# i2c_erm1602_encoder.net
KiCad netlist of a schematic drawn in EAGLE
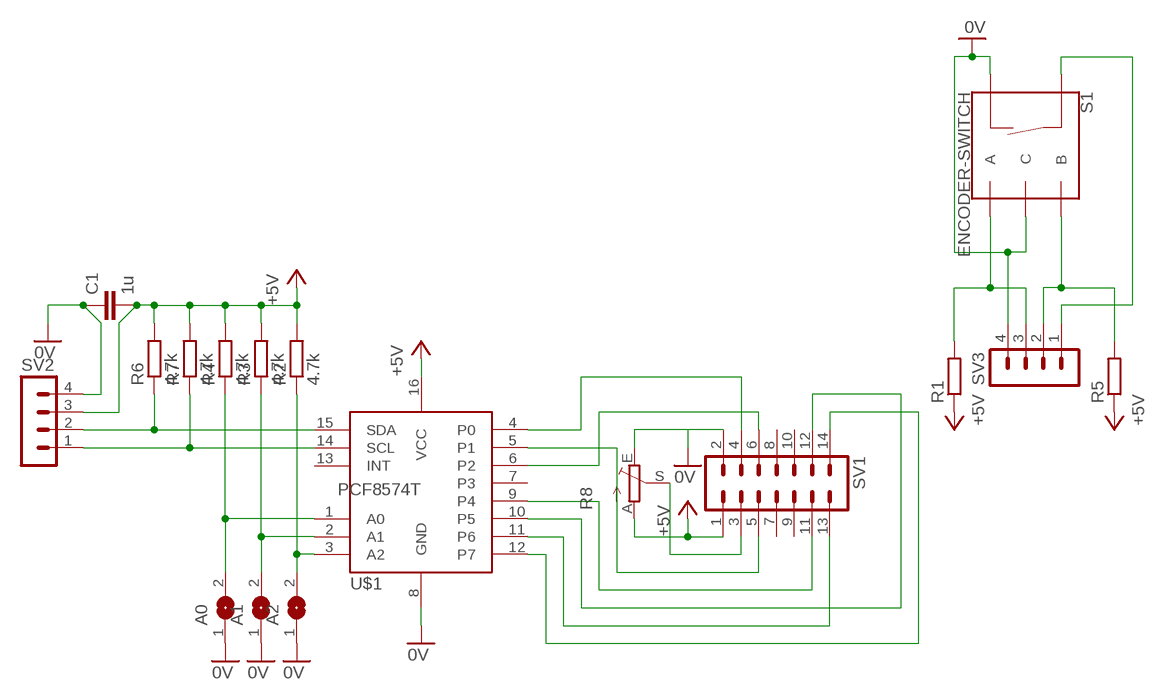
[diagram p0: schematic, sheet 1]

(export (version "E")
  (design (tool "Eeschema 10.0.6"))
  (components
    (comp (ref "A0") (value "SJ") (footprint "eagle-import:SJ") (libsource (lib "eagle-import") (part "SJ")))
    (comp (ref "A1") (value "SJ") (footprint "eagle-import:SJ") (libsource (lib "eagle-import") (part "SJ")))
    (comp (ref "A2") (value "SJ") (footprint "eagle-import:SJ") (libsource (lib "eagle-import") (part "SJ")))
    (comp (ref "C1")
      (value "1u")
      (footprint "eagle-import:C1206K")
      (libsource (lib "eagle-import") (part "C-EUC1206K"))
    )
    (comp (ref "R1")
      (value "R-EU_0204/5")
      (footprint "eagle-import:0204_5")
      (libsource (lib "eagle-import") (part "R-EU_0204/5"))
    )
    (comp (ref "R2")
      (value "4.7k")
      (footprint "eagle-import:0204_5")
      (libsource (lib "eagle-import") (part "R-EU_0204/5"))
    )
    (comp (ref "R3")
      (value "4.7k")
      (footprint "eagle-import:0204_5")
      (libsource (lib "eagle-import") (part "R-EU_0204/5"))
    )
    (comp (ref "R4")
      (value "4.7k")
      (footprint "eagle-import:0204_5")
      (libsource (lib "eagle-import") (part "R-EU_0204/5"))
    )
    (comp (ref "R5")
      (value "R-EU_0204/5")
      (footprint "eagle-import:0204_5")
      (libsource (lib "eagle-import") (part "R-EU_0204/5"))
    )
    (comp (ref "R6")
      (value "4.7k")
      (footprint "eagle-import:0204_5")
      (libsource (lib "eagle-import") (part "R-EU_0204/5"))
    )
    (comp (ref "R7")
      (value "4.7k")
      (footprint "eagle-import:0204_5")
      (libsource (lib "eagle-import") (part "R-EU_0204/5"))
    )
    (comp (ref "R8")
      (value "TRIM_EU-B25P")
      (footprint "eagle-import:B25P")
      (libsource (lib "eagle-import") (part "TRIM_EU-B25P"))
    )
    (comp (ref "S1")
      (value "ENCODER-SWITCH")
      (footprint "eagle-import:ROTARY_ENC_PLAIN")
      (libsource (lib "eagle-import") (part "ENCODER-SWITCH"))
    )
    (comp (ref "SV1")
      (value "MA07-2")
      (footprint "eagle-import:MA07-2")
      (libsource (lib "eagle-import") (part "MA07-2"))
    )
    (comp (ref "SV2")
      (value "MA04-1")
      (footprint "eagle-import:MA04-1")
      (libsource (lib "eagle-import") (part "MA04-1"))
    )
    (comp (ref "SV3")
      (value "MA04-1")
      (footprint "eagle-import:MA04-1")
      (libsource (lib "eagle-import") (part "MA04-1"))
    )
    (comp (ref "U$1")
      (value "PCF8574T")
      (footprint "eagle-import:SOT162")
      (libsource (lib "eagle-import") (part "PCF8574T"))
    )
  )
  (nets
    (net (code "1") (name "+5V") (class "Default")
      (node (ref "C1") (pin "2") (pinfunction "2_2") (pintype "passive"))
      (node (ref "R1") (pin "1") (pinfunction "1_1") (pintype "passive"))
      (node (ref "R2") (pin "2") (pinfunction "2_2") (pintype "passive"))
      (node (ref "R3") (pin "2") (pinfunction "2_2") (pintype "passive"))
      (node (ref "R4") (pin "2") (pinfunction "2_2") (pintype "passive"))
      (node (ref "R5") (pin "1") (pinfunction "1_1") (pintype "passive"))
      (node (ref "R6") (pin "2") (pinfunction "2_2") (pintype "passive"))
      (node (ref "R7") (pin "2") (pinfunction "2_2") (pintype "passive"))
      (node (ref "R8") (pin "A") (pinfunction "A_A") (pintype "passive"))
      (node (ref "SV1") (pin "1") (pinfunction "1_1") (pintype "passive"))
      (node (ref "SV2") (pin "3") (pinfunction "3_3") (pintype "passive"))
      (node (ref "U$1") (pin "16") (pinfunction "VCC_16") (pintype "bidirectional"))
    )
    (net (code "2") (name "0V") (class "Default")
      (node (ref "A0") (pin "1") (pinfunction "1_1") (pintype "passive"))
      (node (ref "A1") (pin "1") (pinfunction "1_1") (pintype "passive"))
      (node (ref "A2") (pin "1") (pinfunction "1_1") (pintype "passive"))
      (node (ref "C1") (pin "1") (pinfunction "1_1") (pintype "passive"))
      (node (ref "R8") (pin "E") (pinfunction "E_E") (pintype "passive"))
      (node (ref "S1") (pin "C") (pinfunction "C_C") (pintype "bidirectional"))
      (node (ref "S1") (pin "SW-") (pinfunction "SW-_SW-") (pintype "bidirectional"))
      (node (ref "SV1") (pin "2") (pinfunction "2_2") (pintype "passive"))
      (node (ref "SV2") (pin "4") (pinfunction "4_4") (pintype "passive"))
      (node (ref "SV3") (pin "4") (pinfunction "4_4") (pintype "passive"))
      (node (ref "U$1") (pin "8") (pinfunction "GND_8") (pintype "bidirectional"))
    )
    (net (code "3") (name "Net-(R1-Pad2)") (class "Default")
      (node (ref "R1") (pin "2") (pinfunction "2_2") (pintype "passive"))
      (node (ref "S1") (pin "A") (pinfunction "A_A") (pintype "bidirectional"))
      (node (ref "SV3") (pin "3") (pinfunction "3_3") (pintype "passive"))
    )
    (net (code "4") (name "Net-(R5-Pad2)") (class "Default")
      (node (ref "R5") (pin "2") (pinfunction "2_2") (pintype "passive"))
      (node (ref "S1") (pin "B") (pinfunction "B_B") (pintype "bidirectional"))
      (node (ref "SV3") (pin "2") (pinfunction "2_2") (pintype "passive"))
    )
    (net (code "5") (name "Net-(R8-PadS)") (class "Default")
      (node (ref "R8") (pin "S") (pinfunction "S_S") (pintype "passive"))
      (node (ref "SV1") (pin "3") (pinfunction "3_3") (pintype "passive"))
    )
    (net (code "6") (name "Net-(S1-PadSW+)") (class "Default")
      (node (ref "S1") (pin "SW+") (pinfunction "SW+_SW+") (pintype "bidirectional"))
      (node (ref "SV3") (pin "1") (pinfunction "1_1") (pintype "passive"))
    )
    (net (code "7") (name "Net-(U$1-A0)") (class "Default")
      (node (ref "A0") (pin "2") (pinfunction "2_2") (pintype "passive"))
      (node (ref "R4") (pin "1") (pinfunction "1_1") (pintype "passive"))
      (node (ref "U$1") (pin "1") (pinfunction "A0_1") (pintype "bidirectional"))
    )
    (net (code "8") (name "Net-(U$1-A1)") (class "Default")
      (node (ref "A1") (pin "2") (pinfunction "2_2") (pintype "passive"))
      (node (ref "R3") (pin "1") (pinfunction "1_1") (pintype "passive"))
      (node (ref "U$1") (pin "2") (pinfunction "A1_2") (pintype "bidirectional"))
    )
    (net (code "9") (name "Net-(U$1-A2)") (class "Default")
      (node (ref "A2") (pin "2") (pinfunction "2_2") (pintype "passive"))
      (node (ref "R2") (pin "1") (pinfunction "1_1") (pintype "passive"))
      (node (ref "U$1") (pin "3") (pinfunction "A2_3") (pintype "bidirectional"))
    )
    (net (code "10") (name "Net-(U$1-P0)") (class "Default")
      (node (ref "SV1") (pin "4") (pinfunction "4_4") (pintype "passive"))
      (node (ref "U$1") (pin "4") (pinfunction "P0_4") (pintype "bidirectional"))
    )
    (net (code "11") (name "Net-(U$1-P1)") (class "Default")
      (node (ref "SV1") (pin "5") (pinfunction "5_5") (pintype "passive"))
      (node (ref "U$1") (pin "5") (pinfunction "P1_5") (pintype "bidirectional"))
    )
    (net (code "12") (name "Net-(U$1-P2)") (class "Default")
      (node (ref "SV1") (pin "6") (pinfunction "6_6") (pintype "passive"))
      (node (ref "U$1") (pin "6") (pinfunction "P2_6") (pintype "bidirectional"))
    )
    (net (code "13") (name "Net-(U$1-P4)") (class "Default")
      (node (ref "SV1") (pin "11") (pinfunction "11_11") (pintype "passive"))
      (node (ref "U$1") (pin "9") (pinfunction "P4_9") (pintype "bidirectional"))
    )
    (net (code "14") (name "Net-(U$1-P5)") (class "Default")
      (node (ref "SV1") (pin "12") (pinfunction "12_12") (pintype "passive"))
      (node (ref "U$1") (pin "10") (pinfunction "P5_10") (pintype "bidirectional"))
    )
    (net (code "15") (name "Net-(U$1-P6)") (class "Default")
      (node (ref "SV1") (pin "13") (pinfunction "13_13") (pintype "passive"))
      (node (ref "U$1") (pin "11") (pinfunction "P6_11") (pintype "bidirectional"))
    )
    (net (code "16") (name "Net-(U$1-P7)") (class "Default")
      (node (ref "SV1") (pin "14") (pinfunction "14_14") (pintype "passive"))
      (node (ref "U$1") (pin "12") (pinfunction "P7_12") (pintype "bidirectional"))
    )
    (net (code "17") (name "Net-(U$1-SCL)") (class "Default")
      (node (ref "R7") (pin "1") (pinfunction "1_1") (pintype "passive"))
      (node (ref "SV2") (pin "1") (pinfunction "1_1") (pintype "passive"))
      (node (ref "U$1") (pin "14") (pinfunction "SCL_14") (pintype "bidirectional"))
    )
    (net (code "18") (name "Net-(U$1-SDA)") (class "Default")
      (node (ref "R6") (pin "1") (pinfunction "1_1") (pintype "passive"))
      (node (ref "SV2") (pin "2") (pinfunction "2_2") (pintype "passive"))
      (node (ref "U$1") (pin "15") (pinfunction "SDA_15") (pintype "bidirectional"))
    )
    (net (code "19") (name "unconnected-(SV1-Pad7)") (class "Default")
      (node (ref "SV1") (pin "7") (pinfunction "7_7") (pintype "passive"))
    )
    (net (code "20") (name "unconnected-(SV1-Pad8)") (class "Default")
      (node (ref "SV1") (pin "8") (pinfunction "8_8") (pintype "passive"))
    )
    (net (code "21") (name "unconnected-(SV1-Pad9)") (class "Default")
      (node (ref "SV1") (pin "9") (pinfunction "9_9") (pintype "passive"))
    )
    (net (code "22") (name "unconnected-(SV1-Pad10)") (class "Default")
      (node (ref "SV1") (pin "10") (pinfunction "10_10") (pintype "passive"))
    )
    (net (code "23") (name "unconnected-(U$1-INT-Pad13)") (class "Default")
      (node (ref "U$1") (pin "13") (pinfunction "INT_13") (pintype "bidirectional"))
    )
    (net (code "24") (name "unconnected-(U$1-P3-Pad7)") (class "Default")
      (node (ref "U$1") (pin "7") (pinfunction "P3_7") (pintype "bidirectional"))
    )
  )
)
